# schematic-ebook-reader_v40.net
KiCad netlist of a schematic drawn in EAGLE
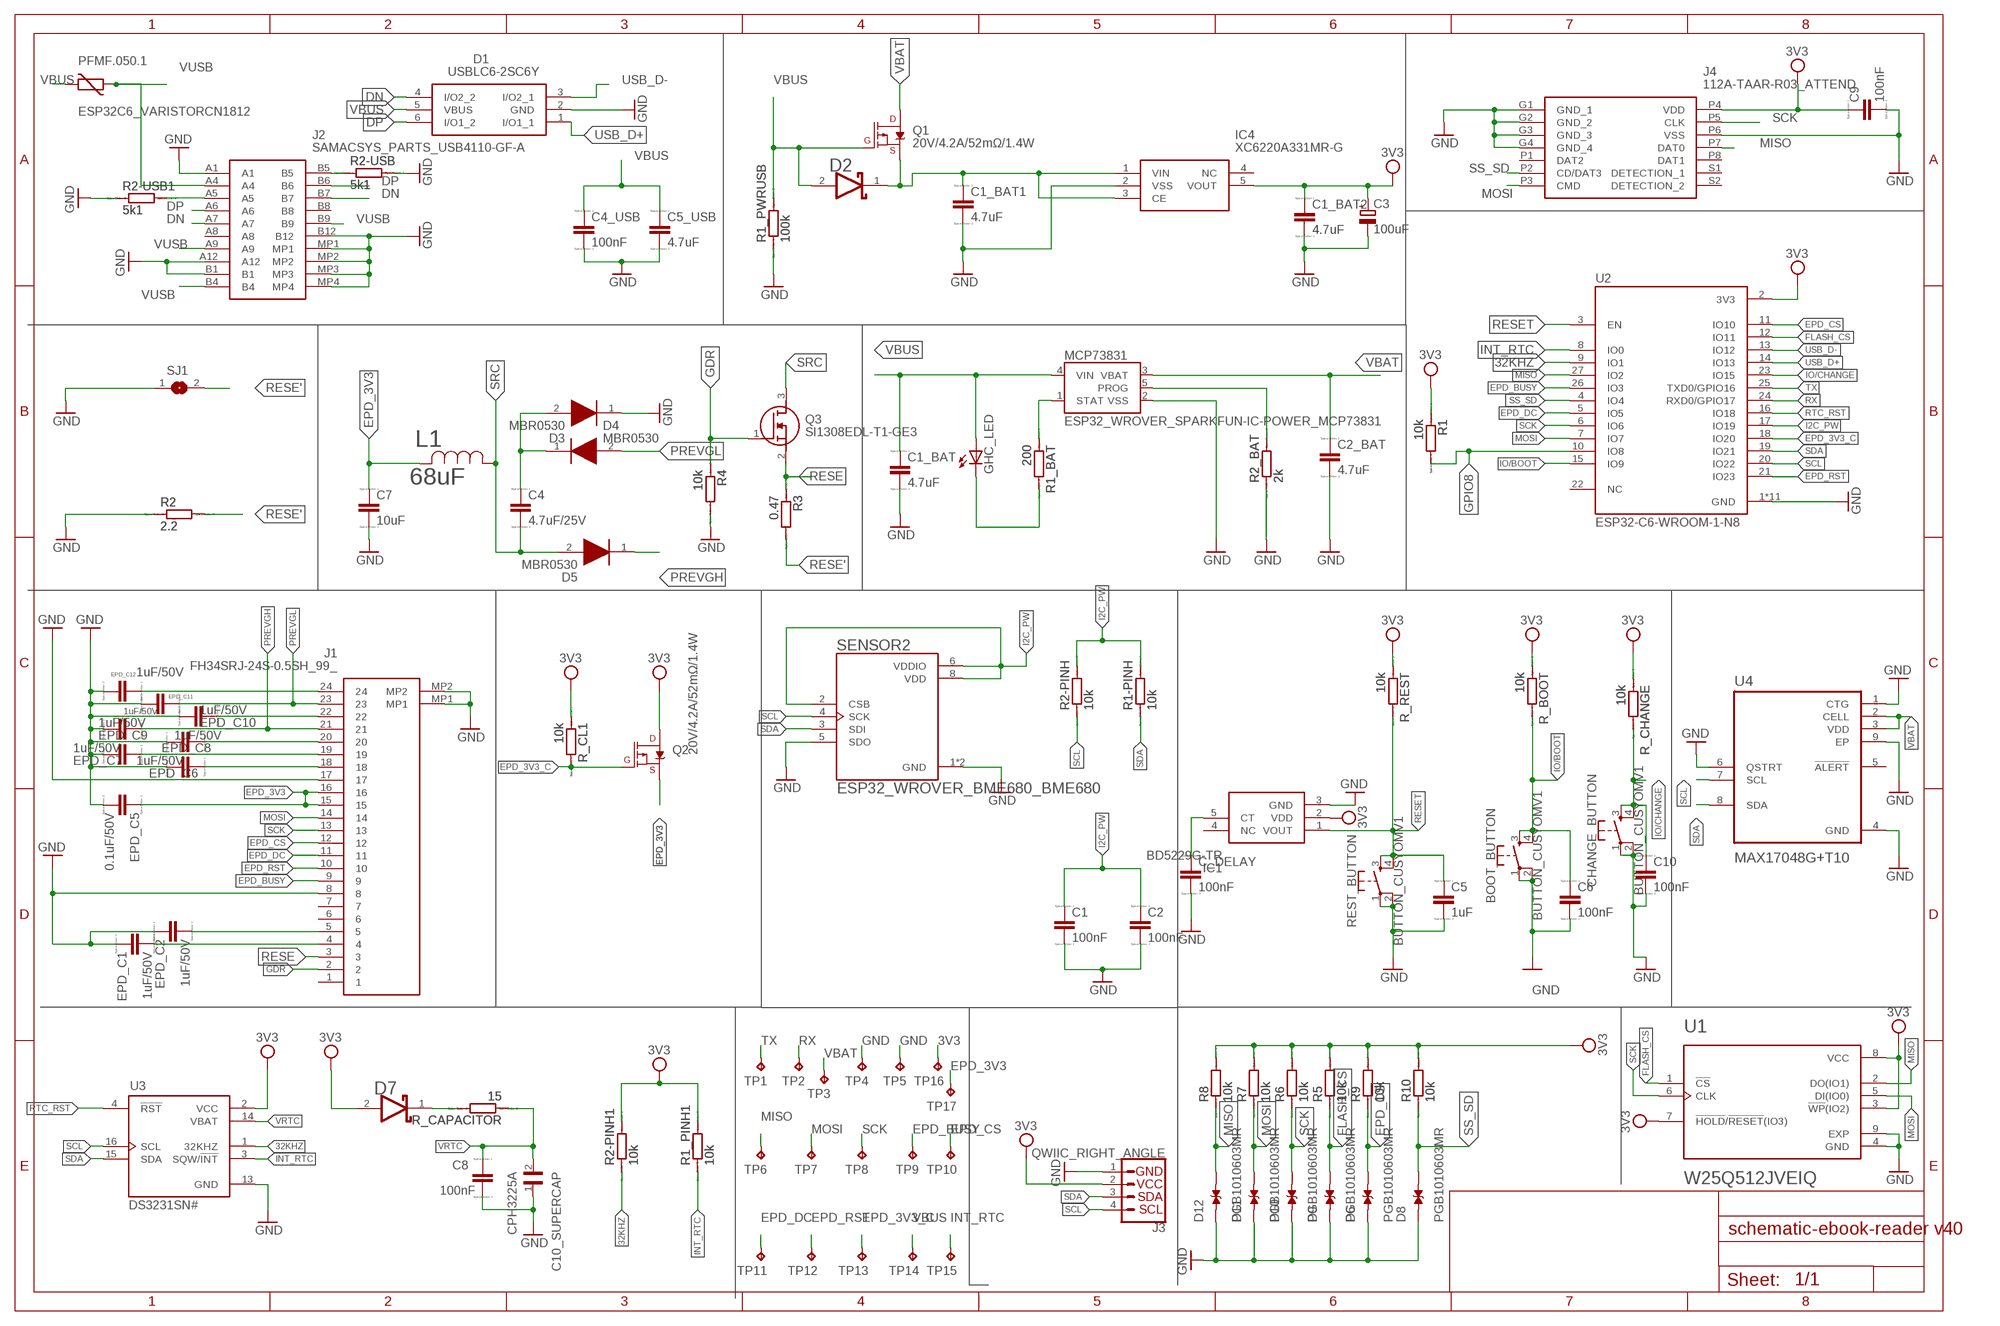
[diagram p0: schematic, sheet 1]

(export (version "E")
  (design (tool "Eeschema 10.0.6"))
  (components
    (comp (ref "BOOT_BUTTON")
      (value "BUTTON_CUSYOMV1")
      (footprint "eagle-import:MYBUTTON")
      (libsource (lib "eagle-import") (part "BUTTON_CUSYOMV1"))
    )
    (comp (ref "C1")
      (value "100nF")
      (footprint "eagle-import:ESP32_WROVER_EAGLE-LTSPICE_C0402")
      (libsource (lib "eagle-import") (part "ESP32_WROVER_EAGLE-LTSPICE_CC0402"))
    )
    (comp (ref "C1_BAT")
      (value "4.7uF")
      (footprint "eagle-import:ESP32_WROVER_EAGLE-LTSPICE_C0402")
      (libsource (lib "eagle-import") (part "ESP32_WROVER_EAGLE-LTSPICE_CC0402"))
    )
    (comp (ref "C1_BAT1")
      (value "4.7uF")
      (footprint "eagle-import:ESP32_WROVER_EAGLE-LTSPICE_C0402")
      (libsource (lib "eagle-import") (part "ESP32_WROVER_EAGLE-LTSPICE_CC0402"))
    )
    (comp (ref "C1_BAT2")
      (value "4.7uF")
      (footprint "eagle-import:ESP32_WROVER_EAGLE-LTSPICE_C0402")
      (libsource (lib "eagle-import") (part "ESP32_WROVER_EAGLE-LTSPICE_CC0402"))
    )
    (comp (ref "C2")
      (value "100nF")
      (footprint "eagle-import:ESP32_WROVER_EAGLE-LTSPICE_C0402")
      (libsource (lib "eagle-import") (part "ESP32_WROVER_EAGLE-LTSPICE_CC0402"))
    )
    (comp (ref "C2_BAT")
      (value "4.7uF")
      (footprint "eagle-import:ESP32_WROVER_EAGLE-LTSPICE_C0402")
      (libsource (lib "eagle-import") (part "ESP32_WROVER_EAGLE-LTSPICE_CC0402"))
    )
    (comp (ref "C3")
      (value "100uF")
      (footprint "eagle-import:RCL_CT3528")
      (libsource (lib "eagle-import") (part "RCL_CPOL-EUCT3528"))
    )
    (comp (ref "C4")
      (value "4.7uF/25V")
      (footprint "eagle-import:ESP32_WROVER_EAGLE-LTSPICE_C0402")
      (libsource (lib "eagle-import") (part "ESP32_WROVER_EAGLE-LTSPICE_CC0402"))
    )
    (comp (ref "C4_USB")
      (value "100nF")
      (footprint "eagle-import:ESP32_WROVER_EAGLE-LTSPICE_C0402")
      (libsource (lib "eagle-import") (part "ESP32_WROVER_EAGLE-LTSPICE_CC0402"))
    )
    (comp (ref "C5")
      (value "1uF")
      (footprint "eagle-import:ESP32_WROVER_EAGLE-LTSPICE_C0402")
      (libsource (lib "eagle-import") (part "ESP32_WROVER_EAGLE-LTSPICE_CC0402"))
    )
    (comp (ref "C5_USB")
      (value "4.7uF")
      (footprint "eagle-import:ESP32_WROVER_EAGLE-LTSPICE_C0402")
      (libsource (lib "eagle-import") (part "ESP32_WROVER_EAGLE-LTSPICE_CC0402"))
    )
    (comp (ref "C6")
      (value "100nF")
      (footprint "eagle-import:ESP32_WROVER_EAGLE-LTSPICE_C0402")
      (libsource (lib "eagle-import") (part "ESP32_WROVER_EAGLE-LTSPICE_CC0402"))
    )
    (comp (ref "C7")
      (value "10uF")
      (footprint "eagle-import:ESP32_WROVER_EAGLE-LTSPICE_C0402")
      (libsource (lib "eagle-import") (part "ESP32_WROVER_EAGLE-LTSPICE_CC0402"))
    )
    (comp (ref "C8")
      (value "100nF")
      (footprint "eagle-import:ESP32_WROVER_EAGLE-LTSPICE_C0402")
      (libsource (lib "eagle-import") (part "ESP32_WROVER_EAGLE-LTSPICE_CC0402"))
    )
    (comp (ref "C9")
      (value "100nF")
      (footprint "eagle-import:ESP32_WROVER_EAGLE-LTSPICE_C0402")
      (libsource (lib "eagle-import") (part "ESP32_WROVER_EAGLE-LTSPICE_CC0402"))
    )
    (comp (ref "C10")
      (value "100nF")
      (footprint "eagle-import:ESP32_WROVER_EAGLE-LTSPICE_C0402")
      (libsource (lib "eagle-import") (part "ESP32_WROVER_EAGLE-LTSPICE_CC0402"))
    )
    (comp (ref "C10_SUPERCAP")
      (value "CPH3225A")
      (footprint "eagle-import:CAPCP3225X100N")
      (fields (field (name "MF") "Seiko Instruments"))
      (libsource (lib "eagle-import") (part "CPH3225A"))
    )
    (comp (ref "CHANGE_BUTTON")
      (value "BUTTON_CUSYOMV1")
      (footprint "eagle-import:MYBUTTON")
      (libsource (lib "eagle-import") (part "BUTTON_CUSYOMV1"))
    )
    (comp (ref "C_DELAY")
      (value "100nF")
      (footprint "eagle-import:ESP32_WROVER_EAGLE-LTSPICE_C0402")
      (libsource (lib "eagle-import") (part "ESP32_WROVER_EAGLE-LTSPICE_CC0402"))
    )
    (comp (ref "D1")
      (value "USBLC6-2SC6Y")
      (footprint "eagle-import:SOT95P280X145-6N")
      (fields (field (name "MF") "STMicroelectronics"))
      (libsource (lib "eagle-import") (part "USBLC6-2SC6Y"))
    )
    (comp (ref "D2")
      (value "ESP32_WROVER_AVX---SD0805S020S1R0_AVX_SD0805S020S1R0_0_0AVX_SD0805S020S1R0_0_0")
      (footprint "eagle-import:ESP32_WROVER_AVX---SD0805S020S1R0_AVX_SD0805S020S1R0_0")
      (fields
        (field (name "DIGIKEY_PART_NUMBER") "478-7800-1-ND")
        (field (name "MF") "AVX")
        (field (name "MOUSER_PART_NUMBER") "581-SD0805S020S1R0")
      )
      (libsource (lib "eagle-import") (part "ESP32_WROVER_AVX---SD0805S020S1R0_AVX_SD0805S020S1R0_0_0AVX_SD0805S020S1R0_0_0"))
    )
    (comp (ref "D3")
      (value "MBR0530")
      (footprint "eagle-import:SOD3716X135N")
      (fields (field (name "MF") "ON Semiconductor"))
      (libsource (lib "eagle-import") (part "MBR0530"))
    )
    (comp (ref "D4")
      (value "MBR0530")
      (footprint "eagle-import:SOD3716X135N")
      (fields (field (name "MF") "ON Semiconductor"))
      (libsource (lib "eagle-import") (part "MBR0530"))
    )
    (comp (ref "D5")
      (value "MBR0530")
      (footprint "eagle-import:SOD3716X135N")
      (fields (field (name "MF") "ON Semiconductor"))
      (libsource (lib "eagle-import") (part "MBR0530"))
    )
    (comp (ref "D6")
      (value "PGB1010603MR")
      (footprint "eagle-import:DIOC1608X36N")
      (fields (field (name "MF") "Littelfuse Inc."))
      (libsource (lib "eagle-import") (part "PGB1010603MR"))
    )
    (comp (ref "D7")
      (value "ESP32_WROVER_AVX---SD0805S020S1R0_AVX_SD0805S020S1R0_0_0AVX_SD0805S020S1R0_0_0")
      (footprint "eagle-import:ESP32_WROVER_AVX---SD0805S020S1R0_AVX_SD0805S020S1R0_0")
      (fields
        (field (name "DIGIKEY_PART_NUMBER") "478-7800-1-ND")
        (field (name "MF") "AVX")
        (field (name "MOUSER_PART_NUMBER") "581-SD0805S020S1R0")
      )
      (libsource (lib "eagle-import") (part "ESP32_WROVER_AVX---SD0805S020S1R0_AVX_SD0805S020S1R0_0_0AVX_SD0805S020S1R0_0_0"))
    )
    (comp (ref "D8")
      (value "PGB1010603MR")
      (footprint "eagle-import:DIOC1608X36N")
      (fields (field (name "MF") "Littelfuse Inc."))
      (libsource (lib "eagle-import") (part "PGB1010603MR"))
    )
    (comp (ref "D9")
      (value "PGB1010603MR")
      (footprint "eagle-import:DIOC1608X36N")
      (fields (field (name "MF") "Littelfuse Inc."))
      (libsource (lib "eagle-import") (part "PGB1010603MR"))
    )
    (comp (ref "D10")
      (value "PGB1010603MR")
      (footprint "eagle-import:DIOC1608X36N")
      (fields (field (name "MF") "Littelfuse Inc."))
      (libsource (lib "eagle-import") (part "PGB1010603MR"))
    )
    (comp (ref "D11")
      (value "PGB1010603MR")
      (footprint "eagle-import:DIOC1608X36N")
      (fields (field (name "MF") "Littelfuse Inc."))
      (libsource (lib "eagle-import") (part "PGB1010603MR"))
    )
    (comp (ref "D12")
      (value "PGB1010603MR")
      (footprint "eagle-import:DIOC1608X36N")
      (fields (field (name "MF") "Littelfuse Inc."))
      (libsource (lib "eagle-import") (part "PGB1010603MR"))
    )
    (comp (ref "EPD_C1")
      (value "1uF/50V")
      (footprint "eagle-import:ESP32_WROVER_EAGLE-LTSPICE_C0402")
      (libsource (lib "eagle-import") (part "ESP32_WROVER_EAGLE-LTSPICE_CC0402"))
    )
    (comp (ref "EPD_C2")
      (value "1uF/50V")
      (footprint "eagle-import:ESP32_WROVER_EAGLE-LTSPICE_C0402")
      (libsource (lib "eagle-import") (part "ESP32_WROVER_EAGLE-LTSPICE_CC0402"))
    )
    (comp (ref "EPD_C5")
      (value "0.1uF/50V")
      (footprint "eagle-import:ESP32_WROVER_EAGLE-LTSPICE_C0402")
      (libsource (lib "eagle-import") (part "ESP32_WROVER_EAGLE-LTSPICE_CC0402"))
    )
    (comp (ref "EPD_C6")
      (value "1uF/50V")
      (footprint "eagle-import:ESP32_WROVER_EAGLE-LTSPICE_C0402")
      (libsource (lib "eagle-import") (part "ESP32_WROVER_EAGLE-LTSPICE_CC0402"))
    )
    (comp (ref "EPD_C7")
      (value "1uF/50V")
      (footprint "eagle-import:ESP32_WROVER_EAGLE-LTSPICE_C0402")
      (libsource (lib "eagle-import") (part "ESP32_WROVER_EAGLE-LTSPICE_CC0402"))
    )
    (comp (ref "EPD_C8")
      (value "1uF/50V")
      (footprint "eagle-import:ESP32_WROVER_EAGLE-LTSPICE_C0402")
      (libsource (lib "eagle-import") (part "ESP32_WROVER_EAGLE-LTSPICE_CC0402"))
    )
    (comp (ref "EPD_C9")
      (value "1uF/50V")
      (footprint "eagle-import:ESP32_WROVER_EAGLE-LTSPICE_C0402")
      (libsource (lib "eagle-import") (part "ESP32_WROVER_EAGLE-LTSPICE_CC0402"))
    )
    (comp (ref "EPD_C10")
      (value "1uF/50V")
      (footprint "eagle-import:ESP32_WROVER_EAGLE-LTSPICE_C0402")
      (libsource (lib "eagle-import") (part "ESP32_WROVER_EAGLE-LTSPICE_CC0402"))
    )
    (comp (ref "EPD_C11")
      (value "1uF/50V")
      (footprint "eagle-import:ESP32_WROVER_EAGLE-LTSPICE_C0402")
      (libsource (lib "eagle-import") (part "ESP32_WROVER_EAGLE-LTSPICE_CC0402"))
    )
    (comp (ref "EPD_C12")
      (value "1uF/50V")
      (footprint "eagle-import:ESP32_WROVER_EAGLE-LTSPICE_C0402")
      (libsource (lib "eagle-import") (part "ESP32_WROVER_EAGLE-LTSPICE_CC0402"))
    )
    (comp (ref "GHC_LED")
      (value "ADAFRUIT_LEDCHIP-LED0603")
      (footprint "eagle-import:ADAFRUIT_CHIP-LED0603")
      (libsource (lib "eagle-import") (part "ADAFRUIT_LEDCHIP-LED0603"))
    )
    (comp (ref "IC1")
      (value "BD5229G-TR")
      (footprint "eagle-import:SOT95P280X125-5N")
      (fields (field (name "MOUSER_PART_NUMBER") "755-BD5229G-TR"))
      (libsource (lib "eagle-import") (part "BD5229G-TR"))
    )
    (comp (ref "IC4")
      (value "XC6220A331MR-G")
      (footprint "eagle-import:SOT95P280X120-5N")
      (fields (field (name "MOUSER_PART_NUMBER") "865-XC6220A331MR-G"))
      (libsource (lib "eagle-import") (part "XC6220A331MR-G"))
    )
    (comp (ref "J1")
      (value "FH34SRJ-24S-0.5SH_99_")
      (footprint "eagle-import:FH34SRJ24S05SH99")
      (fields
        (field (name "MANUFACTURER_PART_NUMBER") "FH34SRJ-24S-0.5SH(99)")
        (field (name "MOUSER_PART_NUMBER") "798-FH34SRJ24S05SH99")
      )
      (libsource (lib "eagle-import") (part "FH34SRJ-24S-0.5SH_99_"))
    )
    (comp (ref "J2")
      (value "SAMACSYS_PARTS_USB4110-GF-A")
      (footprint "eagle-import:SAMACSYS_PARTS_USB4110GFA")
      (fields
        (field (name "MANUFACTURER_PART_NUMBER") "USB4110-GF-A")
        (field (name "MOUSER_PART_NUMBER") "640-USB4110-GF-A")
      )
      (libsource (lib "eagle-import") (part "SAMACSYS_PARTS_USB4110-GF-A"))
    )
    (comp (ref "J3")
      (value "QWIIC_RIGHT_ANGLE")
      (footprint "eagle-import:JST04_1MM_RA")
      (libsource (lib "eagle-import") (part "QWIIC_CONNECTORJS-1MM"))
    )
    (comp (ref "J4")
      (value "112A-TAAR-R03_ATTEND")
      (footprint "eagle-import:112ATAARR03ATTEND")
      (fields (field (name "MANUFACTURER_PART_NUMBER") "112A-TAAR-R03 ATTEND"))
      (libsource (lib "eagle-import") (part "112A-TAAR-R03_ATTEND"))
    )
    (comp (ref "L1")
      (value "68uF")
      (footprint "eagle-import:IND_4828-WE-TPC_WRE")
      (fields
        (field (name "MANUFACTURER_PART_NUMBER") "744043680")
        (field (name "COPYRIGHT") "Copyright (C) 2024 Ultra Librarian. All rights reserved.")
      )
      (libsource (lib "eagle-import") (part "744043680IND_4828-WE-TPC_WRE"))
    )
    (comp (ref "MCP73831")
      (value "ESP32_WROVER_SPARKFUN-IC-POWER_MCP73831")
      (footprint "eagle-import:ESP32_WROVER_SPARKFUN-IC-POWER_SOT23-5")
      (libsource (lib "eagle-import") (part "ESP32_WROVER_SPARKFUN-IC-POWER_MCP73831"))
    )
    (comp (ref "PFMF.050.1")
      (value "ESP32C6_VARISTORCN1812")
      (footprint "eagle-import:ESP32C6_VARISTOR_CT_CN1812")
      (libsource (lib "eagle-import") (part "ESP32C6_VARISTORCN1812"))
    )
    (comp (ref "Q1")
      (value "20V/4.2A/52mΩ/1.4W")
      (footprint "eagle-import:ESP32_WROVER_SPARKFUN-DISCRETESEMI_SOT23-3")
      (libsource (lib "eagle-import") (part "ESP32_WROVER_SPARKFUN-DISCRETESEMI_MOSFET_PCH-DMG2305UX-7"))
    )
    (comp (ref "Q2")
      (value "20V/4.2A/52mΩ/1.4W")
      (footprint "eagle-import:ESP32_WROVER_SPARKFUN-DISCRETESEMI_SOT23-3")
      (libsource (lib "eagle-import") (part "ESP32_WROVER_SPARKFUN-DISCRETESEMI_MOSFET_PCH-DMG2305UX-7"))
    )
    (comp (ref "Q3")
      (value "SI1308EDL-T1-GE3")
      (footprint "eagle-import:SOT65P210X110-3N")
      (fields (field (name "MF") "Vishay Siliconix"))
      (libsource (lib "eagle-import") (part "SI1308EDL-T1-GE3"))
    )
    (comp (ref "R1")
      (value "10k")
      (footprint "eagle-import:ESP32_WROVER_EAGLE-LTSPICE_C0402")
      (libsource (lib "eagle-import") (part "ESP32_WROVER_EAGLE-LTSPICE_RR0402"))
    )
    (comp (ref "R1-PINH")
      (value "10k")
      (footprint "eagle-import:ESP32_WROVER_EAGLE-LTSPICE_C0402")
      (libsource (lib "eagle-import") (part "ESP32_WROVER_EAGLE-LTSPICE_RR0402"))
    )
    (comp (ref "R1_BAT")
      (value "200")
      (footprint "eagle-import:ESP32_WROVER_EAGLE-LTSPICE_C0402")
      (libsource (lib "eagle-import") (part "ESP32_WROVER_EAGLE-LTSPICE_RR0402"))
    )
    (comp (ref "R1_PINH1")
      (value "10k")
      (footprint "eagle-import:ESP32_WROVER_EAGLE-LTSPICE_C0402")
      (libsource (lib "eagle-import") (part "ESP32_WROVER_EAGLE-LTSPICE_RR0402"))
    )
    (comp (ref "R1_PWRUSB")
      (value "100k")
      (footprint "eagle-import:ESP32_WROVER_EAGLE-LTSPICE_C0402")
      (libsource (lib "eagle-import") (part "ESP32_WROVER_EAGLE-LTSPICE_RR0402"))
    )
    (comp (ref "R2")
      (value "2.2")
      (footprint "eagle-import:ESP32_WROVER_EAGLE-LTSPICE_C0402")
      (libsource (lib "eagle-import") (part "ESP32_WROVER_EAGLE-LTSPICE_RR0402"))
    )
    (comp (ref "R2-PINH")
      (value "10k")
      (footprint "eagle-import:ESP32_WROVER_EAGLE-LTSPICE_C0402")
      (libsource (lib "eagle-import") (part "ESP32_WROVER_EAGLE-LTSPICE_RR0402"))
    )
    (comp (ref "R2-PINH1")
      (value "10k")
      (footprint "eagle-import:ESP32_WROVER_EAGLE-LTSPICE_C0402")
      (libsource (lib "eagle-import") (part "ESP32_WROVER_EAGLE-LTSPICE_RR0402"))
    )
    (comp (ref "R2-USB")
      (value "5k1")
      (footprint "eagle-import:ESP32_WROVER_EAGLE-LTSPICE_C0402")
      (libsource (lib "eagle-import") (part "ESP32_WROVER_EAGLE-LTSPICE_RR0402"))
    )
    (comp (ref "R2-USB1")
      (value "5k1")
      (footprint "eagle-import:ESP32_WROVER_EAGLE-LTSPICE_C0402")
      (libsource (lib "eagle-import") (part "ESP32_WROVER_EAGLE-LTSPICE_RR0402"))
    )
    (comp (ref "R2_BAT")
      (value "2k")
      (footprint "eagle-import:ESP32_WROVER_EAGLE-LTSPICE_C0402")
      (libsource (lib "eagle-import") (part "ESP32_WROVER_EAGLE-LTSPICE_RR0402"))
    )
    (comp (ref "R3")
      (value "0.47")
      (footprint "eagle-import:ESP32_WROVER_EAGLE-LTSPICE_C0402")
      (libsource (lib "eagle-import") (part "ESP32_WROVER_EAGLE-LTSPICE_RR0402"))
    )
    (comp (ref "R4")
      (value "10k")
      (footprint "eagle-import:ESP32_WROVER_EAGLE-LTSPICE_C0402")
      (libsource (lib "eagle-import") (part "ESP32_WROVER_EAGLE-LTSPICE_RR0402"))
    )
    (comp (ref "R5")
      (value "10k")
      (footprint "eagle-import:ESP32_WROVER_EAGLE-LTSPICE_C0402")
      (libsource (lib "eagle-import") (part "ESP32_WROVER_EAGLE-LTSPICE_RR0402"))
    )
    (comp (ref "R6")
      (value "10k")
      (footprint "eagle-import:ESP32_WROVER_EAGLE-LTSPICE_C0402")
      (libsource (lib "eagle-import") (part "ESP32_WROVER_EAGLE-LTSPICE_RR0402"))
    )
    (comp (ref "R7")
      (value "10k")
      (footprint "eagle-import:ESP32_WROVER_EAGLE-LTSPICE_C0402")
      (libsource (lib "eagle-import") (part "ESP32_WROVER_EAGLE-LTSPICE_RR0402"))
    )
    (comp (ref "R8")
      (value "10k")
      (footprint "eagle-import:ESP32_WROVER_EAGLE-LTSPICE_C0402")
      (libsource (lib "eagle-import") (part "ESP32_WROVER_EAGLE-LTSPICE_RR0402"))
    )
    (comp (ref "R9")
      (value "10k")
      (footprint "eagle-import:ESP32_WROVER_EAGLE-LTSPICE_C0402")
      (libsource (lib "eagle-import") (part "ESP32_WROVER_EAGLE-LTSPICE_RR0402"))
    )
    (comp (ref "R10")
      (value "10k")
      (footprint "eagle-import:ESP32_WROVER_EAGLE-LTSPICE_C0402")
      (libsource (lib "eagle-import") (part "ESP32_WROVER_EAGLE-LTSPICE_RR0402"))
    )
    (comp (ref "REST_BUTTON")
      (value "BUTTON_CUSYOMV1")
      (footprint "eagle-import:MYBUTTON")
      (libsource (lib "eagle-import") (part "BUTTON_CUSYOMV1"))
    )
    (comp (ref "R_BOOT")
      (value "10k")
      (footprint "eagle-import:ESP32_WROVER_EAGLE-LTSPICE_C0402")
      (libsource (lib "eagle-import") (part "ESP32_WROVER_EAGLE-LTSPICE_RR0402"))
    )
    (comp (ref "R_CAPACITOR")
      (value "15")
      (footprint "eagle-import:ESP32_WROVER_EAGLE-LTSPICE_C0402")
      (libsource (lib "eagle-import") (part "ESP32_WROVER_EAGLE-LTSPICE_RR0402"))
    )
    (comp (ref "R_CHANGE")
      (value "10k")
      (footprint "eagle-import:ESP32_WROVER_EAGLE-LTSPICE_C0402")
      (libsource (lib "eagle-import") (part "ESP32_WROVER_EAGLE-LTSPICE_RR0402"))
    )
    (comp (ref "R_CL1")
      (value "10k")
      (footprint "eagle-import:ESP32_WROVER_EAGLE-LTSPICE_C0402")
      (libsource (lib "eagle-import") (part "ESP32_WROVER_EAGLE-LTSPICE_RR0402"))
    )
    (comp (ref "R_REST")
      (value "10k")
      (footprint "eagle-import:ESP32_WROVER_EAGLE-LTSPICE_C0402")
      (libsource (lib "eagle-import") (part "ESP32_WROVER_EAGLE-LTSPICE_RR0402"))
    )
    (comp (ref "SENSOR2")
      (value "ESP32_WROVER_BME680_BME680")
      (footprint "eagle-import:ESP32_WROVER_BME680_PSON80P300X300X100-8N")
      (fields (field (name "MF") "Bosch Sensortec") (field (name "MP") "BME680"))
      (libsource (lib "eagle-import") (part "ESP32_WROVER_BME680_BME680"))
    )
    (comp (ref "SJ1") (value "SJ") (footprint "eagle-import:SJ") (libsource (lib "eagle-import") (part "SJ")))
    (comp (ref "TP1")
      (value "TPTP20R")
      (footprint "eagle-import:TP20R")
      (libsource (lib "eagle-import") (part "TPTP20R"))
    )
    (comp (ref "TP2")
      (value "TPTP20R")
      (footprint "eagle-import:TP20R")
      (libsource (lib "eagle-import") (part "TPTP20R"))
    )
    (comp (ref "TP3")
      (value "TPTP20R")
      (footprint "eagle-import:TP20R")
      (libsource (lib "eagle-import") (part "TPTP20R"))
    )
    (comp (ref "TP4")
      (value "TPTP20R")
      (footprint "eagle-import:TP20R")
      (libsource (lib "eagle-import") (part "TPTP20R"))
    )
    (comp (ref "TP5")
      (value "TPTP20R")
      (footprint "eagle-import:TP20R")
      (libsource (lib "eagle-import") (part "TPTP20R"))
    )
    (comp (ref "TP6")
      (value "TPTP20R")
      (footprint "eagle-import:TP20R")
      (libsource (lib "eagle-import") (part "TPTP20R"))
    )
    (comp (ref "TP7")
      (value "TPTP20R")
      (footprint "eagle-import:TP20R")
      (libsource (lib "eagle-import") (part "TPTP20R"))
    )
    (comp (ref "TP8")
      (value "TPTP20R")
      (footprint "eagle-import:TP20R")
      (libsource (lib "eagle-import") (part "TPTP20R"))
    )
    (comp (ref "TP9")
      (value "TPTP20R")
      (footprint "eagle-import:TP20R")
      (libsource (lib "eagle-import") (part "TPTP20R"))
    )
    (comp (ref "TP10")
      (value "TPTP20R")
      (footprint "eagle-import:TP20R")
      (libsource (lib "eagle-import") (part "TPTP20R"))
    )
    (comp (ref "TP11")
      (value "TPTP20R")
      (footprint "eagle-import:TP20R")
      (libsource (lib "eagle-import") (part "TPTP20R"))
    )
    (comp (ref "TP12")
      (value "TPTP20R")
      (footprint "eagle-import:TP20R")
      (libsource (lib "eagle-import") (part "TPTP20R"))
    )
    (comp (ref "TP13")
      (value "TPTP20R")
      (footprint "eagle-import:TP20R")
      (libsource (lib "eagle-import") (part "TPTP20R"))
    )
    (comp (ref "TP14")
      (value "TPTP20R")
      (footprint "eagle-import:TP20R")
      (libsource (lib "eagle-import") (part "TPTP20R"))
    )
    (comp (ref "TP15")
      (value "TPTP20R")
      (footprint "eagle-import:TP20R")
      (libsource (lib "eagle-import") (part "TPTP20R"))
    )
    (comp (ref "TP16")
      (value "TPTP20R")
      (footprint "eagle-import:TP20R")
      (libsource (lib "eagle-import") (part "TPTP20R"))
    )
    (comp (ref "TP17")
      (value "TPTP20R")
      (footprint "eagle-import:TP20R")
      (libsource (lib "eagle-import") (part "TPTP20R"))
    )
    (comp (ref "U1")
      (value "W25Q512JVEIQ")
      (footprint "eagle-import:SON127P600X800X80-9N")
      (fields (field (name "MF") "Winbond Electronics"))
      (libsource (lib "eagle-import") (part "W25Q512JVEIQ"))
    )
    (comp (ref "U2")
      (value "ESP32-C6-WROOM-1-N8")
      (footprint "eagle-import:XCVR_ESP32-C6-WROOM-1-N8")
      (fields (field (name "MF") "Espressif Systems"))
      (libsource (lib "eagle-import") (part "ESP32-C6-WROOM-1-N8"))
    )
    (comp (ref "U3")
      (value "DS3231SN#")
      (footprint "eagle-import:SOIC127P1032X265-16N")
      (fields (field (name "MF") "Analog Devices"))
      (libsource (lib "eagle-import") (part "DS3231SN#"))
    )
    (comp (ref "U4")
      (value "MAX17048G+T10")
      (footprint "eagle-import:SON50P200X200X80-9N")
      (fields (field (name "MF") "Analog Devices"))
      (libsource (lib "eagle-import") (part "MAX17048G+T10"))
    )
  )
  (nets
    (net (code "1") (name "/VUSB") (class "Default")
      (node (ref "J2") (pin "A4") (pinfunction "A4_A4") (pintype "bidirectional"))
      (node (ref "J2") (pin "A9") (pinfunction "A9_A9") (pintype "bidirectional"))
      (node (ref "J2") (pin "B4") (pinfunction "B4_B4") (pintype "bidirectional"))
      (node (ref "J2") (pin "B9") (pinfunction "B9_B9") (pintype "bidirectional"))
      (node (ref "PFMF.050.1") (pin "1") (pinfunction "1_1") (pintype "passive"))
    )
    (net (code "2") (name "3V3") (class "Default")
      (node (ref "C1_BAT2") (pin "1") (pinfunction "1_1") (pintype "passive"))
      (node (ref "C3") (pin "+") (pinfunction "+_+") (pintype "passive"))
      (node (ref "C9") (pin "1") (pinfunction "1_1") (pintype "passive"))
      (node (ref "D7") (pin "2") (pinfunction "ANODE_2") (pintype "bidirectional"))
      (node (ref "IC1") (pin "2") (pinfunction "VDD_2") (pintype "bidirectional"))
      (node (ref "IC4") (pin "5") (pinfunction "VOUT_5") (pintype "bidirectional"))
      (node (ref "J3") (pin "2") (pinfunction "2_2") (pintype "power_in"))
      (node (ref "J4") (pin "P4") (pinfunction "VDD_P4") (pintype "bidirectional"))
      (node (ref "Q2") (pin "3") (pinfunction "D_3") (pintype "bidirectional"))
      (node (ref "R1") (pin "1") (pinfunction "1_1") (pintype "passive"))
      (node (ref "R10") (pin "2") (pinfunction "2_2") (pintype "passive"))
      (node (ref "R1_PINH1") (pin "2") (pinfunction "2_2") (pintype "passive"))
      (node (ref "R2-PINH1") (pin "2") (pinfunction "2_2") (pintype "passive"))
      (node (ref "R5") (pin "2") (pinfunction "2_2") (pintype "passive"))
      (node (ref "R6") (pin "2") (pinfunction "2_2") (pintype "passive"))
      (node (ref "R7") (pin "2") (pinfunction "2_2") (pintype "passive"))
      (node (ref "R8") (pin "2") (pinfunction "2_2") (pintype "passive"))
      (node (ref "R9") (pin "2") (pinfunction "2_2") (pintype "passive"))
      (node (ref "R_BOOT") (pin "1") (pinfunction "1_1") (pintype "passive"))
      (node (ref "R_CHANGE") (pin "1") (pinfunction "1_1") (pintype "passive"))
      (node (ref "R_CL1") (pin "1") (pinfunction "1_1") (pintype "passive"))
      (node (ref "R_REST") (pin "1") (pinfunction "1_1") (pintype "passive"))
      (node (ref "TP16") (pin "TP") (pinfunction "TP_TP") (pintype "input"))
      (node (ref "U1") (pin "3") (pinfunction "~{WP}(IO2)_3") (pintype "bidirectional"))
      (node (ref "U1") (pin "7") (pinfunction "~{HOLD}/~{RESET}(IO3)_7") (pintype "bidirectional"))
      (node (ref "U1") (pin "8") (pinfunction "VCC_8") (pintype "power_in"))
      (node (ref "U2") (pin "2") (pinfunction "3V3_2") (pintype "power_in"))
      (node (ref "U3") (pin "2") (pinfunction "VCC_2") (pintype "power_in"))
    )
    (net (code "3") (name "32KHZ") (class "Default")
      (node (ref "R2-PINH1") (pin "1") (pinfunction "1_1") (pintype "passive"))
      (node (ref "U2") (pin "9") (pinfunction "IO1_9") (pintype "bidirectional"))
      (node (ref "U3") (pin "1") (pinfunction "32KHZ_1") (pintype "output"))
    )
    (net (code "4") (name "DN") (class "Default")
      (node (ref "D1") (pin "4") (pinfunction "I/O2_2_4") (pintype "bidirectional"))
      (node (ref "J2") (pin "A7") (pinfunction "A7_A7") (pintype "bidirectional"))
      (node (ref "J2") (pin "B7") (pinfunction "B7_B7") (pintype "bidirectional"))
    )
    (net (code "5") (name "DP") (class "Default")
      (node (ref "D1") (pin "6") (pinfunction "I/O1_2_6") (pintype "bidirectional"))
      (node (ref "J2") (pin "A6") (pinfunction "A6_A6") (pintype "bidirectional"))
      (node (ref "J2") (pin "B6") (pinfunction "B6_B6") (pintype "bidirectional"))
    )
    (net (code "6") (name "EPD_3V3") (class "Default")
      (node (ref "C7") (pin "1") (pinfunction "1_1") (pintype "passive"))
      (node (ref "EPD_C5") (pin "1") (pinfunction "1_1") (pintype "passive"))
      (node (ref "J1") (pin "15") (pinfunction "15_15") (pintype "bidirectional"))
      (node (ref "J1") (pin "16") (pinfunction "16_16") (pintype "bidirectional"))
      (node (ref "L1") (pin "2") (pinfunction "2_2") (pintype "passive"))
      (node (ref "Q2") (pin "2") (pinfunction "S_2") (pintype "bidirectional"))
      (node (ref "TP17") (pin "TP") (pinfunction "TP_TP") (pintype "input"))
    )
    (net (code "7") (name "EPD_3V3_C") (class "Default")
      (node (ref "Q2") (pin "1") (pinfunction "G_1") (pintype "bidirectional"))
      (node (ref "R_CL1") (pin "2") (pinfunction "2_2") (pintype "passive"))
      (node (ref "TP13") (pin "TP") (pinfunction "TP_TP") (pintype "input"))
      (node (ref "U2") (pin "18") (pinfunction "IO20_18") (pintype "bidirectional"))
    )
    (net (code "8") (name "EPD_BUSY") (class "Default")
      (node (ref "J1") (pin "9") (pinfunction "9_9") (pintype "bidirectional"))
      (node (ref "TP9") (pin "TP") (pinfunction "TP_TP") (pintype "input"))
      (node (ref "U2") (pin "26") (pinfunction "IO3_26") (pintype "bidirectional"))
    )
    (net (code "9") (name "EPD_CS") (class "Default")
      (node (ref "D6") (pin "2") (pinfunction "2_2") (pintype "passive"))
      (node (ref "J1") (pin "12") (pinfunction "12_12") (pintype "bidirectional"))
      (node (ref "R9") (pin "1") (pinfunction "1_1") (pintype "passive"))
      (node (ref "TP10") (pin "TP") (pinfunction "TP_TP") (pintype "input"))
      (node (ref "U2") (pin "11") (pinfunction "IO10_11") (pintype "bidirectional"))
    )
    (net (code "10") (name "EPD_DC") (class "Default")
      (node (ref "J1") (pin "11") (pinfunction "11_11") (pintype "bidirectional"))
      (node (ref "TP11") (pin "TP") (pinfunction "TP_TP") (pintype "input"))
      (node (ref "U2") (pin "5") (pinfunction "IO5_5") (pintype "bidirectional"))
    )
    (net (code "11") (name "EPD_RST") (class "Default")
      (node (ref "J1") (pin "10") (pinfunction "10_10") (pintype "bidirectional"))
      (node (ref "TP12") (pin "TP") (pinfunction "TP_TP") (pintype "input"))
      (node (ref "U2") (pin "21") (pinfunction "IO23_21") (pintype "bidirectional"))
    )
    (net (code "12") (name "FLASH_CS") (class "Default")
      (node (ref "D9") (pin "2") (pinfunction "2_2") (pintype "passive"))
      (node (ref "R5") (pin "1") (pinfunction "1_1") (pintype "passive"))
      (node (ref "U1") (pin "1") (pinfunction "~{CS}_1") (pintype "input"))
      (node (ref "U2") (pin "12") (pinfunction "IO11_12") (pintype "bidirectional"))
    )
    (net (code "13") (name "GDR") (class "Default")
      (node (ref "J1") (pin "2") (pinfunction "2_2") (pintype "bidirectional"))
      (node (ref "Q3") (pin "1") (pinfunction "G_1") (pintype "bidirectional"))
      (node (ref "R4") (pin "1") (pinfunction "1_1") (pintype "passive"))
    )
    (net (code "14") (name "GND") (class "Default")
      (node (ref "BOOT_BUTTON") (pin "1") (pinfunction "1_1") (pintype "passive"))
      (node (ref "BOOT_BUTTON") (pin "2") (pinfunction "2_2") (pintype "passive"))
      (node (ref "C1") (pin "2") (pinfunction "2_2") (pintype "passive"))
      (node (ref "C10") (pin "2") (pinfunction "2_2") (pintype "passive"))
      (node (ref "C10_SUPERCAP") (pin "1") (pinfunction "1_1") (pintype "passive"))
      (node (ref "C1_BAT") (pin "2") (pinfunction "2_2") (pintype "passive"))
      (node (ref "C1_BAT1") (pin "2") (pinfunction "2_2") (pintype "passive"))
      (node (ref "C1_BAT2") (pin "2") (pinfunction "2_2") (pintype "passive"))
      (node (ref "C2") (pin "2") (pinfunction "2_2") (pintype "passive"))
      (node (ref "C2_BAT") (pin "2") (pinfunction "2_2") (pintype "passive"))
      (node (ref "C3") (pin "-") (pinfunction "-_-") (pintype "passive"))
      (node (ref "C4_USB") (pin "2") (pinfunction "2_2") (pintype "passive"))
      (node (ref "C5") (pin "2") (pinfunction "2_2") (pintype "passive"))
      (node (ref "C5_USB") (pin "2") (pinfunction "2_2") (pintype "passive"))
      (node (ref "C6") (pin "2") (pinfunction "2_2") (pintype "passive"))
      (node (ref "C7") (pin "2") (pinfunction "2_2") (pintype "passive"))
      (node (ref "C8") (pin "2") (pinfunction "2_2") (pintype "passive"))
      (node (ref "C9") (pin "2") (pinfunction "2_2") (pintype "passive"))
      (node (ref "CHANGE_BUTTON") (pin "1") (pinfunction "1_1") (pintype "passive"))
      (node (ref "CHANGE_BUTTON") (pin "2") (pinfunction "2_2") (pintype "passive"))
      (node (ref "C_DELAY") (pin "2") (pinfunction "2_2") (pintype "passive"))
      (node (ref "D1") (pin "2") (pinfunction "GND_2") (pintype "bidirectional"))
      (node (ref "D10") (pin "1") (pinfunction "1_1") (pintype "passive"))
      (node (ref "D11") (pin "1") (pinfunction "1_1") (pintype "passive"))
      (node (ref "D12") (pin "1") (pinfunction "1_1") (pintype "passive"))
      (node (ref "D3") (pin "1") (pinfunction "K_1") (pintype "bidirectional"))
      (node (ref "D6") (pin "1") (pinfunction "1_1") (pintype "passive"))
      (node (ref "D8") (pin "1") (pinfunction "1_1") (pintype "passive"))
      (node (ref "D9") (pin "1") (pinfunction "1_1") (pintype "passive"))
      (node (ref "EPD_C1") (pin "1") (pinfunction "1_1") (pintype "passive"))
      (node (ref "EPD_C10") (pin "2") (pinfunction "2_2") (pintype "passive"))
      (node (ref "EPD_C11") (pin "2") (pinfunction "2_2") (pintype "passive"))
      (node (ref "EPD_C12") (pin "2") (pinfunction "2_2") (pintype "passive"))
      (node (ref "EPD_C2") (pin "1") (pinfunction "1_1") (pintype "passive"))
      (node (ref "EPD_C5") (pin "2") (pinfunction "2_2") (pintype "passive"))
      (node (ref "EPD_C6") (pin "2") (pinfunction "2_2") (pintype "passive"))
      (node (ref "EPD_C7") (pin "2") (pinfunction "2_2") (pintype "passive"))
      (node (ref "EPD_C8") (pin "2") (pinfunction "2_2") (pintype "passive"))
      (node (ref "EPD_C9") (pin "2") (pinfunction "2_2") (pintype "passive"))
      (node (ref "IC1") (pin "3") (pinfunction "GND_3") (pintype "bidirectional"))
      (node (ref "IC4") (pin "2") (pinfunction "VSS_2") (pintype "bidirectional"))
      (node (ref "J1") (pin "17") (pinfunction "17_17") (pintype "bidirectional"))
      (node (ref "J1") (pin "8") (pinfunction "8_8") (pintype "bidirectional"))
      (node (ref "J1") (pin "MP1") (pinfunction "MP1_MP1") (pintype "bidirectional"))
      (node (ref "J1") (pin "MP2") (pinfunction "MP2_MP2") (pintype "bidirectional"))
      (node (ref "J2") (pin "A1") (pinfunction "A1_A1") (pintype "bidirectional"))
      (node (ref "J2") (pin "A12") (pinfunction "A12_A12") (pintype "bidirectional"))
      (node (ref "J2") (pin "B1") (pinfunction "B1_B1") (pintype "bidirectional"))
      (node (ref "J2") (pin "B12") (pinfunction "B12_B12") (pintype "bidirectional"))
      (node (ref "J2") (pin "MP1") (pinfunction "MP1_MP1") (pintype "bidirectional"))
      (node (ref "J2") (pin "MP2") (pinfunction "MP2_MP2") (pintype "bidirectional"))
      (node (ref "J2") (pin "MP3") (pinfunction "MP3_MP3") (pintype "bidirectional"))
      (node (ref "J2") (pin "MP4") (pinfunction "MP4_MP4") (pintype "bidirectional"))
      (node (ref "J3") (pin "1") (pinfunction "1_1") (pintype "power_in"))
      (node (ref "J4") (pin "G1") (pinfunction "GND_1_G1") (pintype "bidirectional"))
      (node (ref "J4") (pin "G2") (pinfunction "GND_2_G2") (pintype "bidirectional"))
      (node (ref "J4") (pin "G3") (pinfunction "GND_3_G3") (pintype "bidirectional"))
      (node (ref "J4") (pin "G4") (pinfunction "GND_4_G4") (pintype "bidirectional"))
      (node (ref "J4") (pin "P6") (pinfunction "VSS_P6") (pintype "bidirectional"))
      (node (ref "MCP73831") (pin "2") (pinfunction "VSS_2") (pintype "power_in"))
      (node (ref "R1_PWRUSB") (pin "1") (pinfunction "1_1") (pintype "passive"))
      (node (ref "R2") (pin "1") (pinfunction "1_1") (pintype "passive"))
      (node (ref "R2-USB") (pin "2") (pinfunction "2_2") (pintype "passive"))
      (node (ref "R2-USB1") (pin "1") (pinfunction "1_1") (pintype "passive"))
      (node (ref "R2_BAT") (pin "1") (pinfunction "1_1") (pintype "passive"))
      (node (ref "R4") (pin "2") (pinfunction "2_2") (pintype "passive"))
      (node (ref "REST_BUTTON") (pin "1") (pinfunction "1_1") (pintype "passive"))
      (node (ref "REST_BUTTON") (pin "2") (pinfunction "2_2") (pintype "passive"))
      (node (ref "SENSOR2") (pin "1") (pinfunction "GND_1") (pintype "power_in"))
      (node (ref "SENSOR2") (pin "5") (pinfunction "SDO_5") (pintype "bidirectional"))
      (node (ref "SENSOR2") (pin "7") (pinfunction "GND_7") (pintype "power_in"))
      (node (ref "SJ1") (pin "1") (pinfunction "1_1") (pintype "passive"))
      (node (ref "TP4") (pin "TP") (pinfunction "TP_TP") (pintype "input"))
      (node (ref "TP5") (pin "TP") (pinfunction "TP_TP") (pintype "input"))
      (node (ref "U1") (pin "4") (pinfunction "GND_4") (pintype "power_in"))
      (node (ref "U1") (pin "9") (pinfunction "EXP_9") (pintype "passive"))
      (node (ref "U2") (pin "1") (pinfunction "GND_1") (pintype "power_in"))
      (node (ref "U2") (pin "28") (pinfunction "GND_28") (pintype "power_in"))
      (node (ref "U2") (pin "29_1") (pinfunction "GND_29_1") (pintype "power_in"))
      (node (ref "U2") (pin "29_2") (pinfunction "GND_29_2") (pintype "power_in"))
      (node (ref "U2") (pin "29_3") (pinfunction "GND_29_3") (pintype "power_in"))
      (node (ref "U2") (pin "29_4") (pinfunction "GND_29_4") (pintype "power_in"))
      (node (ref "U2") (pin "29_5") (pinfunction "GND_29_5") (pintype "power_in"))
      (node (ref "U2") (pin "29_6") (pinfunction "GND_29_6") (pintype "power_in"))
      (node (ref "U2") (pin "29_7") (pinfunction "GND_29_7") (pintype "power_in"))
      (node (ref "U2") (pin "29_8") (pinfunction "GND_29_8") (pintype "power_in"))
      (node (ref "U2") (pin "29_9") (pinfunction "GND_29_9") (pintype "power_in"))
      (node (ref "U3") (pin "13") (pinfunction "GND_13") (pintype "power_in"))
      (node (ref "U4") (pin "1") (pinfunction "CTG_1") (pintype "power_in"))
      (node (ref "U4") (pin "4") (pinfunction "GND_4") (pintype "power_in"))
      (node (ref "U4") (pin "6") (pinfunction "QSTRT_6") (pintype "input"))
      (node (ref "U4") (pin "9") (pinfunction "EP_9") (pintype "power_in"))
    )
    (net (code "15") (name "GPIO8") (class "Default")
      (node (ref "R1") (pin "2") (pinfunction "2_2") (pintype "passive"))
      (node (ref "U2") (pin "10") (pinfunction "IO8_10") (pintype "bidirectional"))
    )
    (net (code "16") (name "I2C_PW") (class "Default")
      (node (ref "C1") (pin "1") (pinfunction "1_1") (pintype "passive"))
      (node (ref "C2") (pin "1") (pinfunction "1_1") (pintype "passive"))
      (node (ref "R1-PINH") (pin "2") (pinfunction "2_2") (pintype "passive"))
      (node (ref "R2-PINH") (pin "2") (pinfunction "2_2") (pintype "passive"))
      (node (ref "SENSOR2") (pin "2") (pinfunction "CSB_2") (pintype "input"))
      (node (ref "SENSOR2") (pin "6") (pinfunction "VDDIO_6") (pintype "power_in"))
      (node (ref "SENSOR2") (pin "8") (pinfunction "VDD_8") (pintype "power_in"))
      (node (ref "U2") (pin "17") (pinfunction "IO19_17") (pintype "bidirectional"))
    )
    (net (code "17") (name "INT_RTC") (class "Default")
      (node (ref "R1_PINH1") (pin "1") (pinfunction "1_1") (pintype "passive"))
      (node (ref "TP15") (pin "TP") (pinfunction "TP_TP") (pintype "input"))
      (node (ref "U2") (pin "8") (pinfunction "IO0_8") (pintype "bidirectional"))
      (node (ref "U3") (pin "3") (pinfunction "SQW/~{INT}_3") (pintype "output"))
    )
    (net (code "18") (name "IO{slash}BOOT") (class "Default")
      (node (ref "BOOT_BUTTON") (pin "3") (pinfunction "3_3") (pintype "passive"))
      (node (ref "BOOT_BUTTON") (pin "4") (pinfunction "4_4") (pintype "passive"))
      (node (ref "C6") (pin "1") (pinfunction "1_1") (pintype "passive"))
      (node (ref "R_BOOT") (pin "2") (pinfunction "2_2") (pintype "passive"))
      (node (ref "U2") (pin "15") (pinfunction "IO9_15") (pintype "bidirectional"))
    )
    (net (code "19") (name "IO{slash}CHANGE") (class "Default")
      (node (ref "C10") (pin "1") (pinfunction "1_1") (pintype "passive"))
      (node (ref "CHANGE_BUTTON") (pin "3") (pinfunction "3_3") (pintype "passive"))
      (node (ref "CHANGE_BUTTON") (pin "4") (pinfunction "4_4") (pintype "passive"))
      (node (ref "R_CHANGE") (pin "2") (pinfunction "2_2") (pintype "passive"))
      (node (ref "U2") (pin "23") (pinfunction "IO15_23") (pintype "bidirectional"))
    )
    (net (code "20") (name "MISO") (class "Default")
      (node (ref "D12") (pin "2") (pinfunction "2_2") (pintype "passive"))
      (node (ref "J4") (pin "P7") (pinfunction "DAT0_P7") (pintype "bidirectional"))
      (node (ref "R8") (pin "1") (pinfunction "1_1") (pintype "passive"))
      (node (ref "TP6") (pin "TP") (pinfunction "TP_TP") (pintype "input"))
      (node (ref "U1") (pin "2") (pinfunction "DO(IO1)_2") (pintype "bidirectional"))
      (node (ref "U2") (pin "27") (pinfunction "IO2_27") (pintype "bidirectional"))
    )
    (net (code "21") (name "MOSI") (class "Default")
      (node (ref "D11") (pin "2") (pinfunction "2_2") (pintype "passive"))
      (node (ref "J1") (pin "14") (pinfunction "14_14") (pintype "bidirectional"))
      (node (ref "J4") (pin "P3") (pinfunction "CMD_P3") (pintype "bidirectional"))
      (node (ref "R7") (pin "1") (pinfunction "1_1") (pintype "passive"))
      (node (ref "TP7") (pin "TP") (pinfunction "TP_TP") (pintype "input"))
      (node (ref "U1") (pin "5") (pinfunction "DI(IO0)_5") (pintype "bidirectional"))
      (node (ref "U2") (pin "7") (pinfunction "IO7_7") (pintype "bidirectional"))
    )
    (net (code "22") (name "Net-(D2-CATHODE)") (class "Default")
      (node (ref "C1_BAT1") (pin "1") (pinfunction "1_1") (pintype "passive"))
      (node (ref "D2") (pin "1") (pinfunction "CATHODE_1") (pintype "bidirectional"))
      (node (ref "IC4") (pin "1") (pinfunction "VIN_1") (pintype "bidirectional"))
      (node (ref "IC4") (pin "3") (pinfunction "CE_3") (pintype "bidirectional"))
      (node (ref "Q1") (pin "2") (pinfunction "S_2") (pintype "bidirectional"))
    )
    (net (code "23") (name "Net-(D3-A)") (class "Default")
      (node (ref "C4") (pin "1") (pinfunction "1_1") (pintype "passive"))
      (node (ref "D3") (pin "2") (pinfunction "A_2") (pintype "bidirectional"))
      (node (ref "D4") (pin "1") (pinfunction "K_1") (pintype "bidirectional"))
    )
    (net (code "24") (name "Net-(D7-CATHODE)") (class "Default")
      (node (ref "D7") (pin "1") (pinfunction "CATHODE_1") (pintype "bidirectional"))
      (node (ref "R_CAPACITOR") (pin "2") (pinfunction "2_2") (pintype "passive"))
    )
    (net (code "25") (name "Net-(EPD_C1-Pad2)") (class "Default")
      (node (ref "EPD_C1") (pin "2") (pinfunction "2_2") (pintype "passive"))
      (node (ref "J1") (pin "4") (pinfunction "4_4") (pintype "bidirectional"))
    )
    (net (code "26") (name "Net-(EPD_C2-Pad2)") (class "Default")
      (node (ref "EPD_C2") (pin "2") (pinfunction "2_2") (pintype "passive"))
      (node (ref "J1") (pin "5") (pinfunction "5_5") (pintype "bidirectional"))
    )
    (net (code "27") (name "Net-(EPD_C6-Pad1)") (class "Default")
      (node (ref "EPD_C6") (pin "1") (pinfunction "1_1") (pintype "passive"))
      (node (ref "J1") (pin "18") (pinfunction "18_18") (pintype "bidirectional"))
    )
    (net (code "28") (name "Net-(EPD_C7-Pad1)") (class "Default")
      (node (ref "EPD_C7") (pin "1") (pinfunction "1_1") (pintype "passive"))
      (node (ref "J1") (pin "19") (pinfunction "19_19") (pintype "bidirectional"))
    )
    (net (code "29") (name "Net-(EPD_C8-Pad1)") (class "Default")
      (node (ref "EPD_C8") (pin "1") (pinfunction "1_1") (pintype "passive"))
      (node (ref "J1") (pin "20") (pinfunction "20_20") (pintype "bidirectional"))
    )
    (net (code "30") (name "Net-(EPD_C10-Pad1)") (class "Default")
      (node (ref "EPD_C10") (pin "1") (pinfunction "1_1") (pintype "passive"))
      (node (ref "J1") (pin "22") (pinfunction "22_22") (pintype "bidirectional"))
    )
    (net (code "31") (name "Net-(EPD_C12-Pad1)") (class "Default")
      (node (ref "EPD_C12") (pin "1") (pinfunction "1_1") (pintype "passive"))
      (node (ref "J1") (pin "24") (pinfunction "24_24") (pintype "bidirectional"))
    )
    (net (code "32") (name "Net-(GHC_LED-PadC)") (class "Default")
      (node (ref "GHC_LED") (pin "C") (pinfunction "C_C") (pintype "passive"))
      (node (ref "R1_BAT") (pin "2") (pinfunction "2_2") (pintype "passive"))
    )
    (net (code "33") (name "Net-(IC1-CT)") (class "Default")
      (node (ref "C_DELAY") (pin "1") (pinfunction "1_1") (pintype "passive"))
      (node (ref "IC1") (pin "5") (pinfunction "CT_5") (pintype "bidirectional"))
    )
    (net (code "34") (name "Net-(J2-PadA5)") (class "Default")
      (node (ref "J2") (pin "A5") (pinfunction "A5_A5") (pintype "bidirectional"))
      (node (ref "R2-USB1") (pin "2") (pinfunction "2_2") (pintype "passive"))
    )
    (net (code "35") (name "Net-(J2-PadB5)") (class "Default")
      (node (ref "J2") (pin "B5") (pinfunction "B5_B5") (pintype "bidirectional"))
      (node (ref "R2-USB") (pin "1") (pinfunction "1_1") (pintype "passive"))
    )
    (net (code "36") (name "Net-(MCP73831-PROG)") (class "Default")
      (node (ref "MCP73831") (pin "5") (pinfunction "PROG_5") (pintype "input"))
      (node (ref "R2_BAT") (pin "2") (pinfunction "2_2") (pintype "passive"))
    )
    (net (code "37") (name "Net-(MCP73831-STAT)") (class "Default")
      (node (ref "MCP73831") (pin "1") (pinfunction "STAT_1") (pintype "output"))
      (node (ref "R1_BAT") (pin "1") (pinfunction "1_1") (pintype "passive"))
    )
    (net (code "38") (name "PREVGH") (class "Default")
      (node (ref "D5") (pin "1") (pinfunction "K_1") (pintype "bidirectional"))
      (node (ref "EPD_C9") (pin "1") (pinfunction "1_1") (pintype "passive"))
      (node (ref "J1") (pin "21") (pinfunction "21_21") (pintype "bidirectional"))
    )
    (net (code "39") (name "PREVGL") (class "Default")
      (node (ref "D4") (pin "2") (pinfunction "A_2") (pintype "bidirectional"))
      (node (ref "EPD_C11") (pin "1") (pinfunction "1_1") (pintype "passive"))
      (node (ref "J1") (pin "23") (pinfunction "23_23") (pintype "bidirectional"))
    )
    (net (code "40") (name "RESE") (class "Default")
      (node (ref "J1") (pin "3") (pinfunction "3_3") (pintype "bidirectional"))
      (node (ref "Q3") (pin "2") (pinfunction "S_2") (pintype "bidirectional"))
      (node (ref "R3") (pin "1") (pinfunction "1_1") (pintype "passive"))
    )
    (net (code "41") (name "RESE'") (class "Default")
      (node (ref "R2") (pin "2") (pinfunction "2_2") (pintype "passive"))
      (node (ref "R3") (pin "2") (pinfunction "2_2") (pintype "passive"))
      (node (ref "SJ1") (pin "2") (pinfunction "2_2") (pintype "passive"))
    )
    (net (code "42") (name "RESET") (class "Default")
      (node (ref "C5") (pin "1") (pinfunction "1_1") (pintype "passive"))
      (node (ref "IC1") (pin "1") (pinfunction "VOUT_1") (pintype "bidirectional"))
      (node (ref "REST_BUTTON") (pin "3") (pinfunction "3_3") (pintype "passive"))
      (node (ref "REST_BUTTON") (pin "4") (pinfunction "4_4") (pintype "passive"))
      (node (ref "R_REST") (pin "2") (pinfunction "2_2") (pintype "passive"))
      (node (ref "U2") (pin "3") (pinfunction "EN_3") (pintype "input"))
    )
    (net (code "43") (name "RTC_RST") (class "Default")
      (node (ref "U2") (pin "16") (pinfunction "IO18_16") (pintype "bidirectional"))
      (node (ref "U3") (pin "4") (pinfunction "~{RST}_4") (pintype "input"))
    )
    (net (code "44") (name "RX") (class "Default")
      (node (ref "TP2") (pin "TP") (pinfunction "TP_TP") (pintype "input"))
      (node (ref "U2") (pin "24") (pinfunction "RXD0/GPIO17_24") (pintype "bidirectional"))
    )
    (net (code "45") (name "SCK") (class "Default")
      (node (ref "D10") (pin "2") (pinfunction "2_2") (pintype "passive"))
      (node (ref "J1") (pin "13") (pinfunction "13_13") (pintype "bidirectional"))
      (node (ref "J4") (pin "P5") (pinfunction "CLK_P5") (pintype "bidirectional"))
      (node (ref "R6") (pin "1") (pinfunction "1_1") (pintype "passive"))
      (node (ref "TP8") (pin "TP") (pinfunction "TP_TP") (pintype "input"))
      (node (ref "U1") (pin "6") (pinfunction "CLK_6") (pintype "input"))
      (node (ref "U2") (pin "6") (pinfunction "IO6_6") (pintype "bidirectional"))
    )
    (net (code "46") (name "SCL") (class "Default")
      (node (ref "J3") (pin "4") (pinfunction "4_4") (pintype "passive"))
      (node (ref "R2-PINH") (pin "1") (pinfunction "1_1") (pintype "passive"))
      (node (ref "SENSOR2") (pin "4") (pinfunction "SCK_4") (pintype "input"))
      (node (ref "U2") (pin "20") (pinfunction "IO22_20") (pintype "bidirectional"))
      (node (ref "U3") (pin "16") (pinfunction "SCL_16") (pintype "input"))
      (node (ref "U4") (pin "7") (pinfunction "SCL_7") (pintype "input"))
    )
    (net (code "47") (name "SDA") (class "Default")
      (node (ref "J3") (pin "3") (pinfunction "3_3") (pintype "passive"))
      (node (ref "R1-PINH") (pin "1") (pinfunction "1_1") (pintype "passive"))
      (node (ref "SENSOR2") (pin "3") (pinfunction "SDI_3") (pintype "bidirectional"))
      (node (ref "U2") (pin "19") (pinfunction "IO21_19") (pintype "bidirectional"))
      (node (ref "U3") (pin "15") (pinfunction "SDA_15") (pintype "bidirectional"))
      (node (ref "U4") (pin "8") (pinfunction "SDA_8") (pintype "bidirectional"))
    )
    (net (code "48") (name "SRC") (class "Default")
      (node (ref "C4") (pin "2") (pinfunction "2_2") (pintype "passive"))
      (node (ref "D5") (pin "2") (pinfunction "A_2") (pintype "bidirectional"))
      (node (ref "L1") (pin "1") (pinfunction "1_1") (pintype "passive"))
      (node (ref "Q3") (pin "3") (pinfunction "D_3") (pintype "bidirectional"))
    )
    (net (code "49") (name "SS_SD") (class "Default")
      (node (ref "D8") (pin "2") (pinfunction "2_2") (pintype "passive"))
      (node (ref "J4") (pin "P2") (pinfunction "CD/DAT3_P2") (pintype "bidirectional"))
      (node (ref "R10") (pin "1") (pinfunction "1_1") (pintype "passive"))
      (node (ref "U2") (pin "4") (pinfunction "IO4_4") (pintype "bidirectional"))
    )
    (net (code "50") (name "TX") (class "Default")
      (node (ref "TP1") (pin "TP") (pinfunction "TP_TP") (pintype "input"))
      (node (ref "U2") (pin "25") (pinfunction "TXD0/GPIO16_25") (pintype "bidirectional"))
    )
    (net (code "51") (name "USB_D+") (class "Default")
      (node (ref "D1") (pin "1") (pinfunction "I/O1_1_1") (pintype "bidirectional"))
      (node (ref "U2") (pin "14") (pinfunction "IO13_14") (pintype "bidirectional"))
    )
    (net (code "52") (name "USB_D-") (class "Default")
      (node (ref "D1") (pin "3") (pinfunction "I/O2_1_3") (pintype "bidirectional"))
      (node (ref "U2") (pin "13") (pinfunction "IO12_13") (pintype "bidirectional"))
    )
    (net (code "53") (name "VBAT") (class "Default")
      (node (ref "C2_BAT") (pin "1") (pinfunction "1_1") (pintype "passive"))
      (node (ref "MCP73831") (pin "3") (pinfunction "VBAT_3") (pintype "power_in"))
      (node (ref "Q1") (pin "3") (pinfunction "D_3") (pintype "bidirectional"))
      (node (ref "TP3") (pin "TP") (pinfunction "TP_TP") (pintype "input"))
      (node (ref "U4") (pin "2") (pinfunction "CELL_2") (pintype "power_in"))
      (node (ref "U4") (pin "3") (pinfunction "VDD_3") (pintype "power_in"))
    )
    (net (code "54") (name "VBUS") (class "Default")
      (node (ref "C1_BAT") (pin "1") (pinfunction "1_1") (pintype "passive"))
      (node (ref "C4_USB") (pin "1") (pinfunction "1_1") (pintype "passive"))
      (node (ref "C5_USB") (pin "1") (pinfunction "1_1") (pintype "passive"))
      (node (ref "D1") (pin "5") (pinfunction "VBUS_5") (pintype "bidirectional"))
      (node (ref "D2") (pin "2") (pinfunction "ANODE_2") (pintype "bidirectional"))
      (node (ref "GHC_LED") (pin "A") (pinfunction "A_A") (pintype "passive"))
      (node (ref "MCP73831") (pin "4") (pinfunction "VIN_4") (pintype "power_in"))
      (node (ref "PFMF.050.1") (pin "2") (pinfunction "2_2") (pintype "passive"))
      (node (ref "Q1") (pin "1") (pinfunction "G_1") (pintype "bidirectional"))
      (node (ref "R1_PWRUSB") (pin "2") (pinfunction "2_2") (pintype "passive"))
      (node (ref "TP14") (pin "TP") (pinfunction "TP_TP") (pintype "input"))
    )
    (net (code "55") (name "VRTC") (class "Default")
      (node (ref "C10_SUPERCAP") (pin "2") (pinfunction "2_2") (pintype "passive"))
      (node (ref "C8") (pin "1") (pinfunction "1_1") (pintype "passive"))
      (node (ref "R_CAPACITOR") (pin "1") (pinfunction "1_1") (pintype "passive"))
      (node (ref "U3") (pin "14") (pinfunction "VBAT_14") (pintype "power_in"))
    )
    (net (code "56") (name "unconnected-(IC1-NC-Pad4)") (class "Default")
      (node (ref "IC1") (pin "4") (pinfunction "NC_4") (pintype "no_connect"))
    )
    (net (code "57") (name "unconnected-(IC4-NC-Pad4)") (class "Default")
      (node (ref "IC4") (pin "4") (pinfunction "NC_4") (pintype "no_connect"))
    )
    (net (code "58") (name "unconnected-(J1-Pad1)") (class "Default")
      (node (ref "J1") (pin "1") (pinfunction "1_1") (pintype "bidirectional"))
    )
    (net (code "59") (name "unconnected-(J1-Pad6)") (class "Default")
      (node (ref "J1") (pin "6") (pinfunction "6_6") (pintype "bidirectional"))
    )
    (net (code "60") (name "unconnected-(J1-Pad7)") (class "Default")
      (node (ref "J1") (pin "7") (pinfunction "7_7") (pintype "bidirectional"))
    )
    (net (code "61") (name "unconnected-(J2-PadA8)") (class "Default")
      (node (ref "J2") (pin "A8") (pinfunction "A8_A8") (pintype "bidirectional"))
    )
    (net (code "62") (name "unconnected-(J2-PadB8)") (class "Default")
      (node (ref "J2") (pin "B8") (pinfunction "B8_B8") (pintype "bidirectional"))
    )
    (net (code "63") (name "unconnected-(J4-DAT1-PadP8)") (class "Default")
      (node (ref "J4") (pin "P8") (pinfunction "DAT1_P8") (pintype "bidirectional"))
    )
    (net (code "64") (name "unconnected-(J4-DAT2-PadP1)") (class "Default")
      (node (ref "J4") (pin "P1") (pinfunction "DAT2_P1") (pintype "bidirectional"))
    )
    (net (code "65") (name "unconnected-(J4-DETECTION_1-PadS1)") (class "Default")
      (node (ref "J4") (pin "S1") (pinfunction "DETECTION_1_S1") (pintype "bidirectional"))
    )
    (net (code "66") (name "unconnected-(J4-DETECTION_2-PadS2)") (class "Default")
      (node (ref "J4") (pin "S2") (pinfunction "DETECTION_2_S2") (pintype "bidirectional"))
    )
    (net (code "67") (name "unconnected-(U2-NC-Pad22)") (class "Default")
      (node (ref "U2") (pin "22") (pinfunction "NC_22") (pintype "no_connect"))
    )
    (net (code "68") (name "unconnected-(U4-~{ALERT}-Pad5)") (class "Default")
      (node (ref "U4") (pin "5") (pinfunction "~{ALERT}_5") (pintype "output"))
    )
  )
)
